# satshakit-grbl.net
KiCad netlist of a schematic drawn in EAGLE
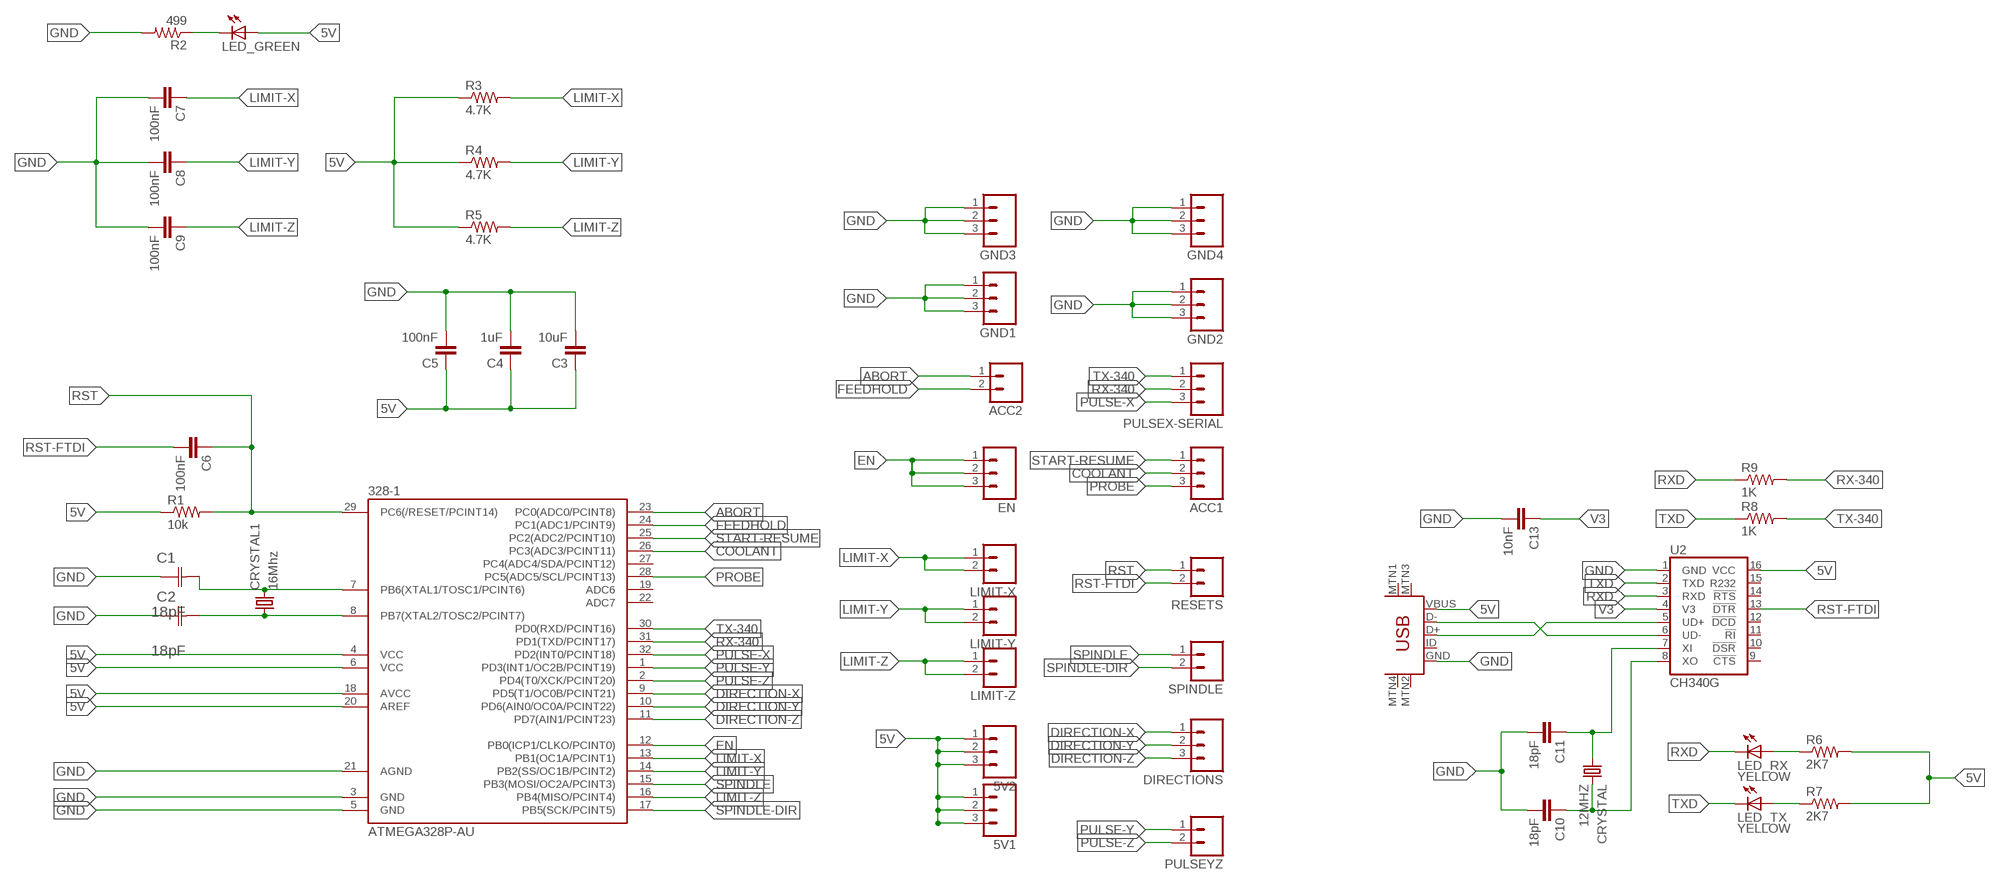
[diagram p0: schematic, sheet 1]

(export (version "E")
  (design (tool "Eeschema 10.0.6"))
  (components
    (comp (ref "5V1")
      (value "M03")
      (footprint "eagle-import:03P")
      (libsource (lib "eagle-import") (part "M03"))
    )
    (comp (ref "5V2")
      (value "M03")
      (footprint "eagle-import:03P")
      (libsource (lib "eagle-import") (part "M03"))
    )
    (comp (ref "328-1")
      (value "ATMEGA328P-AU")
      (footprint "eagle-import:TQFP32-08")
      (libsource (lib "eagle-import") (part "ATMEGA48/88/168-AU"))
    )
    (comp (ref "ACC1")
      (value "M03")
      (footprint "eagle-import:03P")
      (libsource (lib "eagle-import") (part "M03"))
    )
    (comp (ref "ACC2")
      (value "M02")
      (footprint "eagle-import:02P")
      (libsource (lib "eagle-import") (part "M02"))
    )
    (comp (ref "C1")
      (value "18pF")
      (footprint "eagle-import:CAPC3216X178N")
      (fields (field (name "MPN") "0612ZC225MAT2A") (field (name "TOLERANCE") "±20%"))
      (libsource (lib "eagle-import") (part "0612ZC225MAT2A"))
    )
    (comp (ref "C2")
      (value "18pF")
      (footprint "eagle-import:CAPC3216X178N")
      (fields (field (name "MPN") "0612ZC225MAT2A") (field (name "TOLERANCE") "±20%"))
      (libsource (lib "eagle-import") (part "0612ZC225MAT2A"))
    )
    (comp (ref "C3")
      (value "10uF")
      (footprint "eagle-import:1206")
      (libsource (lib "eagle-import") (part "CAP1206"))
    )
    (comp (ref "C4")
      (value "1uF")
      (footprint "eagle-import:1206")
      (libsource (lib "eagle-import") (part "CAP1206"))
    )
    (comp (ref "C5")
      (value "100nF")
      (footprint "eagle-import:1206")
      (libsource (lib "eagle-import") (part "CAP1206"))
    )
    (comp (ref "C6")
      (value "100nF")
      (footprint "eagle-import:1206")
      (libsource (lib "eagle-import") (part "CAP1206"))
    )
    (comp (ref "C7")
      (value "100nF")
      (footprint "eagle-import:1206")
      (libsource (lib "eagle-import") (part "CAP1206"))
    )
    (comp (ref "C8")
      (value "100nF")
      (footprint "eagle-import:1206")
      (libsource (lib "eagle-import") (part "CAP1206"))
    )
    (comp (ref "C9")
      (value "100nF")
      (footprint "eagle-import:1206")
      (libsource (lib "eagle-import") (part "CAP1206"))
    )
    (comp (ref "C10")
      (value "18pF")
      (footprint "eagle-import:1206")
      (libsource (lib "eagle-import") (part "CAP1206"))
    )
    (comp (ref "C11")
      (value "18pF")
      (footprint "eagle-import:1206")
      (libsource (lib "eagle-import") (part "CAP1206"))
    )
    (comp (ref "C13")
      (value "10nF")
      (footprint "eagle-import:1206")
      (libsource (lib "eagle-import") (part "CAP1206"))
    )
    (comp (ref "CRYSTAL")
      (value "12MHZ")
      (footprint "eagle-import:CSM-7X-DU")
      (libsource (lib "eagle-import") (part "flight_controller.lbr01_FAB_Hello_CSM-7X-DU"))
    )
    (comp (ref "CRYSTAL1")
      (value "16Mhz")
      (footprint "eagle-import:CSM-7X-DU")
      (libsource (lib "eagle-import") (part "CSM-7X-DU"))
    )
    (comp (ref "DIRECTIONS")
      (value "M03")
      (footprint "eagle-import:03P")
      (libsource (lib "eagle-import") (part "M03"))
    )
    (comp (ref "EN")
      (value "M03")
      (footprint "eagle-import:03P")
      (libsource (lib "eagle-import") (part "M03"))
    )
    (comp (ref "GND1")
      (value "M03")
      (footprint "eagle-import:03P")
      (libsource (lib "eagle-import") (part "M03"))
    )
    (comp (ref "GND2")
      (value "M03")
      (footprint "eagle-import:03P")
      (libsource (lib "eagle-import") (part "M03"))
    )
    (comp (ref "GND3")
      (value "M03")
      (footprint "eagle-import:03P")
      (libsource (lib "eagle-import") (part "M03"))
    )
    (comp (ref "GND4")
      (value "M03")
      (footprint "eagle-import:03P")
      (libsource (lib "eagle-import") (part "M03"))
    )
    (comp (ref "LED_GREEN")
      (value "LED1206")
      (footprint "eagle-import:1206")
      (libsource (lib "eagle-import") (part "LED1206"))
    )
    (comp (ref "LED_RX")
      (value "YELLOW")
      (footprint "eagle-import:LED1206")
      (libsource (lib "eagle-import") (part "LED"))
    )
    (comp (ref "LED_TX")
      (value "YELLOW")
      (footprint "eagle-import:LED1206")
      (libsource (lib "eagle-import") (part "LED"))
    )
    (comp (ref "LIMIT-X")
      (value "M02")
      (footprint "eagle-import:02P")
      (libsource (lib "eagle-import") (part "M02"))
    )
    (comp (ref "LIMIT-Y")
      (value "M02")
      (footprint "eagle-import:02P")
      (libsource (lib "eagle-import") (part "M02"))
    )
    (comp (ref "LIMIT-Z")
      (value "M02")
      (footprint "eagle-import:02P")
      (libsource (lib "eagle-import") (part "M02"))
    )
    (comp (ref "PULSEX-SERIAL")
      (value "M03")
      (footprint "eagle-import:03P")
      (libsource (lib "eagle-import") (part "M03"))
    )
    (comp (ref "PULSEYZ")
      (value "M02")
      (footprint "eagle-import:02P")
      (libsource (lib "eagle-import") (part "M02"))
    )
    (comp (ref "R1")
      (value "10k")
      (footprint "eagle-import:1206")
      (libsource (lib "eagle-import") (part "RESISTOR1206"))
    )
    (comp (ref "R2")
      (value "499")
      (footprint "eagle-import:1206")
      (libsource (lib "eagle-import") (part "RESISTOR1206"))
    )
    (comp (ref "R3")
      (value "4.7K")
      (footprint "eagle-import:1206")
      (libsource (lib "eagle-import") (part "RESISTOR1206"))
    )
    (comp (ref "R4")
      (value "4.7K")
      (footprint "eagle-import:1206")
      (libsource (lib "eagle-import") (part "RESISTOR1206"))
    )
    (comp (ref "R5")
      (value "4.7K")
      (footprint "eagle-import:1206")
      (libsource (lib "eagle-import") (part "RESISTOR1206"))
    )
    (comp (ref "R6")
      (value "2K7")
      (footprint "eagle-import:R1206")
      (libsource (lib "eagle-import") (part "RES-US1206"))
    )
    (comp (ref "R7")
      (value "2K7")
      (footprint "eagle-import:R1206")
      (libsource (lib "eagle-import") (part "RES-US1206"))
    )
    (comp (ref "R8")
      (value "1K")
      (footprint "eagle-import:R1206")
      (libsource (lib "eagle-import") (part "RES-US1206"))
    )
    (comp (ref "R9")
      (value "1K")
      (footprint "eagle-import:R1206")
      (libsource (lib "eagle-import") (part "RES-US1206"))
    )
    (comp (ref "RESETS")
      (value "M02")
      (footprint "eagle-import:02P")
      (libsource (lib "eagle-import") (part "M02"))
    )
    (comp (ref "SPINDLE")
      (value "M02")
      (footprint "eagle-import:02P")
      (libsource (lib "eagle-import") (part "M02"))
    )
    (comp (ref "U$7")
      (value "USB-MINIB-5PIN")
      (footprint "eagle-import:USB-MINIB")
      (libsource (lib "eagle-import") (part "USB-MINIB-5PIN"))
    )
    (comp (ref "U2")
      (value "CH340G")
      (footprint "eagle-import:SO016")
      (libsource (lib "eagle-import") (part "CH340GSMD"))
    )
  )
  (nets
    (net (code "1") (name "5V") (class "Default")
      (node (ref "328-1") (pin "18") (pinfunction "AVCC_18") (pintype "passive"))
      (node (ref "328-1") (pin "20") (pinfunction "AREF_20") (pintype "passive"))
      (node (ref "328-1") (pin "4") (pinfunction "VCC_4") (pintype "power_in"))
      (node (ref "328-1") (pin "6") (pinfunction "VCC_6") (pintype "power_in"))
      (node (ref "5V1") (pin "1") (pinfunction "1_1") (pintype "passive"))
      (node (ref "5V1") (pin "2") (pinfunction "2_2") (pintype "passive"))
      (node (ref "5V1") (pin "3") (pinfunction "3_3") (pintype "passive"))
      (node (ref "5V2") (pin "1") (pinfunction "1_1") (pintype "passive"))
      (node (ref "5V2") (pin "2") (pinfunction "2_2") (pintype "passive"))
      (node (ref "5V2") (pin "3") (pinfunction "3_3") (pintype "passive"))
      (node (ref "C3") (pin "1") (pinfunction "1_1") (pintype "passive"))
      (node (ref "C4") (pin "1") (pinfunction "1_1") (pintype "passive"))
      (node (ref "C5") (pin "1") (pinfunction "1_1") (pintype "passive"))
      (node (ref "LED_GREEN") (pin "1") (pinfunction "A_1") (pintype "passive"))
      (node (ref "R1") (pin "1") (pinfunction "1_1") (pintype "passive"))
      (node (ref "R3") (pin "1") (pinfunction "1_1") (pintype "passive"))
      (node (ref "R4") (pin "1") (pinfunction "1_1") (pintype "passive"))
      (node (ref "R5") (pin "1") (pinfunction "1_1") (pintype "passive"))
      (node (ref "R6") (pin "2") (pinfunction "2_2") (pintype "passive"))
      (node (ref "R7") (pin "2") (pinfunction "2_2") (pintype "passive"))
      (node (ref "U$7") (pin "VBUS") (pinfunction "VBUS_VBUS") (pintype "bidirectional"))
      (node (ref "U2") (pin "16") (pinfunction "VCC_16") (pintype "bidirectional"))
    )
    (net (code "2") (name "ABORT") (class "Default")
      (node (ref "328-1") (pin "23") (pinfunction "PC0(ADC0/PCINT8)_23") (pintype "bidirectional"))
      (node (ref "ACC2") (pin "1") (pinfunction "1_1") (pintype "passive"))
    )
    (net (code "3") (name "COOLANT") (class "Default")
      (node (ref "328-1") (pin "26") (pinfunction "PC3(ADC3/PCINT11)_26") (pintype "bidirectional"))
      (node (ref "ACC1") (pin "2") (pinfunction "2_2") (pintype "passive"))
    )
    (net (code "4") (name "DIRECTION-X") (class "Default")
      (node (ref "328-1") (pin "9") (pinfunction "PD5(T1/OC0B/PCINT21)_9") (pintype "bidirectional"))
      (node (ref "DIRECTIONS") (pin "1") (pinfunction "1_1") (pintype "passive"))
    )
    (net (code "5") (name "DIRECTION-Y") (class "Default")
      (node (ref "328-1") (pin "10") (pinfunction "PD6(AIN0/OC0A/PCINT22)_10") (pintype "bidirectional"))
      (node (ref "DIRECTIONS") (pin "2") (pinfunction "2_2") (pintype "passive"))
    )
    (net (code "6") (name "DIRECTION-Z") (class "Default")
      (node (ref "328-1") (pin "11") (pinfunction "PD7(AIN1/PCINT23)_11") (pintype "bidirectional"))
      (node (ref "DIRECTIONS") (pin "3") (pinfunction "3_3") (pintype "passive"))
    )
    (net (code "7") (name "EN") (class "Default")
      (node (ref "328-1") (pin "12") (pinfunction "PB0(ICP1/CLKO/PCINT0)_12") (pintype "bidirectional"))
      (node (ref "EN") (pin "1") (pinfunction "1_1") (pintype "passive"))
      (node (ref "EN") (pin "2") (pinfunction "2_2") (pintype "passive"))
      (node (ref "EN") (pin "3") (pinfunction "3_3") (pintype "passive"))
    )
    (net (code "8") (name "FEEDHOLD") (class "Default")
      (node (ref "328-1") (pin "24") (pinfunction "PC1(ADC1/PCINT9)_24") (pintype "bidirectional"))
      (node (ref "ACC2") (pin "2") (pinfunction "2_2") (pintype "passive"))
    )
    (net (code "9") (name "GND") (class "Default")
      (node (ref "328-1") (pin "21") (pinfunction "AGND_21") (pintype "power_in"))
      (node (ref "328-1") (pin "3") (pinfunction "GND_3") (pintype "power_in"))
      (node (ref "328-1") (pin "5") (pinfunction "GND_5") (pintype "power_in"))
      (node (ref "C1") (pin "1") (pinfunction "C1_1") (pintype "passive"))
      (node (ref "C10") (pin "2") (pinfunction "2_2") (pintype "passive"))
      (node (ref "C11") (pin "2") (pinfunction "2_2") (pintype "passive"))
      (node (ref "C13") (pin "2") (pinfunction "2_2") (pintype "passive"))
      (node (ref "C2") (pin "1") (pinfunction "C1_1") (pintype "passive"))
      (node (ref "C3") (pin "2") (pinfunction "2_2") (pintype "passive"))
      (node (ref "C4") (pin "2") (pinfunction "2_2") (pintype "passive"))
      (node (ref "C5") (pin "2") (pinfunction "2_2") (pintype "passive"))
      (node (ref "C7") (pin "2") (pinfunction "2_2") (pintype "passive"))
      (node (ref "C8") (pin "2") (pinfunction "2_2") (pintype "passive"))
      (node (ref "C9") (pin "2") (pinfunction "2_2") (pintype "passive"))
      (node (ref "GND1") (pin "1") (pinfunction "1_1") (pintype "passive"))
      (node (ref "GND1") (pin "2") (pinfunction "2_2") (pintype "passive"))
      (node (ref "GND1") (pin "3") (pinfunction "3_3") (pintype "passive"))
      (node (ref "GND2") (pin "1") (pinfunction "1_1") (pintype "passive"))
      (node (ref "GND2") (pin "2") (pinfunction "2_2") (pintype "passive"))
      (node (ref "GND2") (pin "3") (pinfunction "3_3") (pintype "passive"))
      (node (ref "GND3") (pin "1") (pinfunction "1_1") (pintype "passive"))
      (node (ref "GND3") (pin "2") (pinfunction "2_2") (pintype "passive"))
      (node (ref "GND3") (pin "3") (pinfunction "3_3") (pintype "passive"))
      (node (ref "GND4") (pin "1") (pinfunction "1_1") (pintype "passive"))
      (node (ref "GND4") (pin "2") (pinfunction "2_2") (pintype "passive"))
      (node (ref "GND4") (pin "3") (pinfunction "3_3") (pintype "passive"))
      (node (ref "R2") (pin "2") (pinfunction "2_2") (pintype "passive"))
      (node (ref "U$7") (pin "GND") (pinfunction "GND_GND") (pintype "bidirectional"))
      (node (ref "U2") (pin "1") (pinfunction "GND_1") (pintype "bidirectional"))
    )
    (net (code "10") (name "LIMIT-X") (class "Default")
      (node (ref "328-1") (pin "13") (pinfunction "PB1(OC1A/PCINT1)_13") (pintype "bidirectional"))
      (node (ref "C7") (pin "1") (pinfunction "1_1") (pintype "passive"))
      (node (ref "LIMIT-X") (pin "1") (pinfunction "1_1") (pintype "passive"))
      (node (ref "LIMIT-X") (pin "2") (pinfunction "2_2") (pintype "passive"))
      (node (ref "R3") (pin "2") (pinfunction "2_2") (pintype "passive"))
    )
    (net (code "11") (name "LIMIT-Y") (class "Default")
      (node (ref "328-1") (pin "14") (pinfunction "PB2(SS/OC1B/PCINT2)_14") (pintype "bidirectional"))
      (node (ref "C8") (pin "1") (pinfunction "1_1") (pintype "passive"))
      (node (ref "LIMIT-Y") (pin "1") (pinfunction "1_1") (pintype "passive"))
      (node (ref "LIMIT-Y") (pin "2") (pinfunction "2_2") (pintype "passive"))
      (node (ref "R4") (pin "2") (pinfunction "2_2") (pintype "passive"))
    )
    (net (code "12") (name "LIMIT-Z") (class "Default")
      (node (ref "328-1") (pin "16") (pinfunction "PB4(MISO/PCINT4)_16") (pintype "bidirectional"))
      (node (ref "C9") (pin "1") (pinfunction "1_1") (pintype "passive"))
      (node (ref "LIMIT-Z") (pin "1") (pinfunction "1_1") (pintype "passive"))
      (node (ref "LIMIT-Z") (pin "2") (pinfunction "2_2") (pintype "passive"))
      (node (ref "R5") (pin "2") (pinfunction "2_2") (pintype "passive"))
    )
    (net (code "13") (name "Net-(328-1-PB6(XTAL1{slash}TOSC1{slash}PCINT6))") (class "Default")
      (node (ref "328-1") (pin "7") (pinfunction "PB6(XTAL1/TOSC1/PCINT6)_7") (pintype "bidirectional"))
      (node (ref "C1") (pin "2") (pinfunction "C2_2") (pintype "passive"))
      (node (ref "CRYSTAL1") (pin "2") (pinfunction "2_2") (pintype "passive"))
    )
    (net (code "14") (name "Net-(328-1-PB7(XTAL2{slash}TOSC2{slash}PCINT7))") (class "Default")
      (node (ref "328-1") (pin "8") (pinfunction "PB7(XTAL2/TOSC2/PCINT7)_8") (pintype "bidirectional"))
      (node (ref "C2") (pin "2") (pinfunction "C2_2") (pintype "passive"))
      (node (ref "CRYSTAL1") (pin "1") (pinfunction "1_1") (pintype "passive"))
    )
    (net (code "15") (name "Net-(LED_GREEN-C)") (class "Default")
      (node (ref "LED_GREEN") (pin "2") (pinfunction "C_2") (pintype "passive"))
      (node (ref "R2") (pin "1") (pinfunction "1_1") (pintype "passive"))
    )
    (net (code "16") (name "Net-(LED_RX-A)") (class "Default")
      (node (ref "LED_RX") (pin "1") (pinfunction "A_1") (pintype "passive"))
      (node (ref "R6") (pin "1") (pinfunction "1_1") (pintype "passive"))
    )
    (net (code "17") (name "Net-(LED_TX-A)") (class "Default")
      (node (ref "LED_TX") (pin "1") (pinfunction "A_1") (pintype "passive"))
      (node (ref "R7") (pin "1") (pinfunction "1_1") (pintype "passive"))
    )
    (net (code "18") (name "Net-(U2-UD+)") (class "Default")
      (node (ref "U$7") (pin "D+") (pinfunction "D+_D+") (pintype "bidirectional"))
      (node (ref "U2") (pin "5") (pinfunction "UD+_5") (pintype "bidirectional"))
    )
    (net (code "19") (name "Net-(U2-UD-)") (class "Default")
      (node (ref "U$7") (pin "D-") (pinfunction "D-_D-") (pintype "bidirectional"))
      (node (ref "U2") (pin "6") (pinfunction "UD-_6") (pintype "bidirectional"))
    )
    (net (code "20") (name "Net-(U2-XI)") (class "Default")
      (node (ref "C11") (pin "1") (pinfunction "1_1") (pintype "passive"))
      (node (ref "CRYSTAL") (pin "1") (pinfunction "1_1") (pintype "passive"))
      (node (ref "U2") (pin "7") (pinfunction "XI_7") (pintype "bidirectional"))
    )
    (net (code "21") (name "Net-(U2-XO)") (class "Default")
      (node (ref "C10") (pin "1") (pinfunction "1_1") (pintype "passive"))
      (node (ref "CRYSTAL") (pin "2") (pinfunction "2_2") (pintype "passive"))
      (node (ref "U2") (pin "8") (pinfunction "XO_8") (pintype "bidirectional"))
    )
    (net (code "22") (name "PROBE") (class "Default")
      (node (ref "328-1") (pin "28") (pinfunction "PC5(ADC5/SCL/PCINT13)_28") (pintype "bidirectional"))
      (node (ref "ACC1") (pin "3") (pinfunction "3_3") (pintype "passive"))
    )
    (net (code "23") (name "PULSE-X") (class "Default")
      (node (ref "328-1") (pin "32") (pinfunction "PD2(INT0/PCINT18)_32") (pintype "bidirectional"))
      (node (ref "PULSEX-SERIAL") (pin "3") (pinfunction "3_3") (pintype "passive"))
    )
    (net (code "24") (name "PULSE-Y") (class "Default")
      (node (ref "328-1") (pin "1") (pinfunction "PD3(INT1/OC2B/PCINT19)_1") (pintype "bidirectional"))
      (node (ref "PULSEYZ") (pin "1") (pinfunction "1_1") (pintype "passive"))
    )
    (net (code "25") (name "PULSE-Z") (class "Default")
      (node (ref "328-1") (pin "2") (pinfunction "PD4(T0/XCK/PCINT20)_2") (pintype "bidirectional"))
      (node (ref "PULSEYZ") (pin "2") (pinfunction "2_2") (pintype "passive"))
    )
    (net (code "26") (name "RST") (class "Default")
      (node (ref "328-1") (pin "29") (pinfunction "PC6(/RESET/PCINT14)_29") (pintype "bidirectional"))
      (node (ref "C6") (pin "1") (pinfunction "1_1") (pintype "passive"))
      (node (ref "R1") (pin "2") (pinfunction "2_2") (pintype "passive"))
      (node (ref "RESETS") (pin "1") (pinfunction "1_1") (pintype "passive"))
    )
    (net (code "27") (name "RST-FTDI") (class "Default")
      (node (ref "C6") (pin "2") (pinfunction "2_2") (pintype "passive"))
      (node (ref "RESETS") (pin "2") (pinfunction "2_2") (pintype "passive"))
      (node (ref "U2") (pin "13") (pinfunction "~{DTR}_13") (pintype "bidirectional"))
    )
    (net (code "28") (name "RX-340") (class "Default")
      (node (ref "328-1") (pin "31") (pinfunction "PD1(TXD/PCINT17)_31") (pintype "bidirectional"))
      (node (ref "PULSEX-SERIAL") (pin "2") (pinfunction "2_2") (pintype "passive"))
      (node (ref "R9") (pin "2") (pinfunction "2_2") (pintype "passive"))
    )
    (net (code "29") (name "RXD") (class "Default")
      (node (ref "LED_RX") (pin "2") (pinfunction "C_2") (pintype "passive"))
      (node (ref "R9") (pin "1") (pinfunction "1_1") (pintype "passive"))
      (node (ref "U2") (pin "3") (pinfunction "RXD_3") (pintype "bidirectional"))
    )
    (net (code "30") (name "SPINDLE") (class "Default")
      (node (ref "328-1") (pin "15") (pinfunction "PB3(MOSI/OC2A/PCINT3)_15") (pintype "bidirectional"))
      (node (ref "SPINDLE") (pin "1") (pinfunction "1_1") (pintype "passive"))
    )
    (net (code "31") (name "SPINDLE-DIR") (class "Default")
      (node (ref "328-1") (pin "17") (pinfunction "PB5(SCK/PCINT5)_17") (pintype "bidirectional"))
      (node (ref "SPINDLE") (pin "2") (pinfunction "2_2") (pintype "passive"))
    )
    (net (code "32") (name "START-RESUME") (class "Default")
      (node (ref "328-1") (pin "25") (pinfunction "PC2(ADC2/PCINT10)_25") (pintype "bidirectional"))
      (node (ref "ACC1") (pin "1") (pinfunction "1_1") (pintype "passive"))
    )
    (net (code "33") (name "TX-340") (class "Default")
      (node (ref "328-1") (pin "30") (pinfunction "PD0(RXD/PCINT16)_30") (pintype "bidirectional"))
      (node (ref "PULSEX-SERIAL") (pin "1") (pinfunction "1_1") (pintype "passive"))
      (node (ref "R8") (pin "2") (pinfunction "2_2") (pintype "passive"))
    )
    (net (code "34") (name "TXD") (class "Default")
      (node (ref "LED_TX") (pin "2") (pinfunction "C_2") (pintype "passive"))
      (node (ref "R8") (pin "1") (pinfunction "1_1") (pintype "passive"))
      (node (ref "U2") (pin "2") (pinfunction "TXD_2") (pintype "bidirectional"))
    )
    (net (code "35") (name "V3") (class "Default")
      (node (ref "C13") (pin "1") (pinfunction "1_1") (pintype "passive"))
      (node (ref "U2") (pin "4") (pinfunction "V3_4") (pintype "bidirectional"))
    )
    (net (code "36") (name "unconnected-(328-1-ADC6-Pad19)") (class "Default")
      (node (ref "328-1") (pin "19") (pinfunction "ADC6_19") (pintype "passive"))
    )
    (net (code "37") (name "unconnected-(328-1-ADC7-Pad22)") (class "Default")
      (node (ref "328-1") (pin "22") (pinfunction "ADC7_22") (pintype "passive"))
    )
    (net (code "38") (name "unconnected-(328-1-PC4(ADC4{slash}SDA{slash}PCINT12)-Pad27)") (class "Default")
      (node (ref "328-1") (pin "27") (pinfunction "PC4(ADC4/SDA/PCINT12)_27") (pintype "bidirectional"))
    )
    (net (code "39") (name "unconnected-(U$7-MTN1-PadMTN3)") (class "Default")
      (node (ref "U$7") (pin "MTN3") (pinfunction "MTN1_MTN3") (pintype "bidirectional"))
    )
    (net (code "40") (name "unconnected-(U$7-MTN2-PadMTN1)") (class "Default")
      (node (ref "U$7") (pin "MTN1") (pinfunction "MTN2_MTN1") (pintype "bidirectional"))
    )
    (net (code "41") (name "unconnected-(U$7-MTN3-PadMTN2)") (class "Default")
      (node (ref "U$7") (pin "MTN2") (pinfunction "MTN3_MTN2") (pintype "bidirectional"))
    )
    (net (code "42") (name "unconnected-(U$7-PadID)") (class "Default")
      (node (ref "U$7") (pin "ID") (pinfunction "ID_ID") (pintype "bidirectional"))
    )
    (net (code "43") (name "unconnected-(U$7-PadMTN4)") (class "Default")
      (node (ref "U$7") (pin "MTN4") (pinfunction "MTN4_MTN4") (pintype "bidirectional"))
    )
    (net (code "44") (name "unconnected-(U2-R232-Pad15)") (class "Default")
      (node (ref "U2") (pin "15") (pinfunction "R232_15") (pintype "bidirectional"))
    )
    (net (code "45") (name "unconnected-(U2-~{CTS}-Pad9)") (class "Default")
      (node (ref "U2") (pin "9") (pinfunction "~{CTS}_9") (pintype "bidirectional"))
    )
    (net (code "46") (name "unconnected-(U2-~{DCD}-Pad12)") (class "Default")
      (node (ref "U2") (pin "12") (pinfunction "~{DCD}_12") (pintype "bidirectional"))
    )
    (net (code "47") (name "unconnected-(U2-~{DSR}-Pad10)") (class "Default")
      (node (ref "U2") (pin "10") (pinfunction "~{DSR}_10") (pintype "bidirectional"))
    )
    (net (code "48") (name "unconnected-(U2-~{RI}-Pad11)") (class "Default")
      (node (ref "U2") (pin "11") (pinfunction "~{RI}_11") (pintype "bidirectional"))
    )
    (net (code "49") (name "unconnected-(U2-~{RTS}-Pad14)") (class "Default")
      (node (ref "U2") (pin "14") (pinfunction "~{RTS}_14") (pintype "bidirectional"))
    )
  )
)
